# miscellaneous.net
KiCad netlist of a schematic drawn in Altium Designer
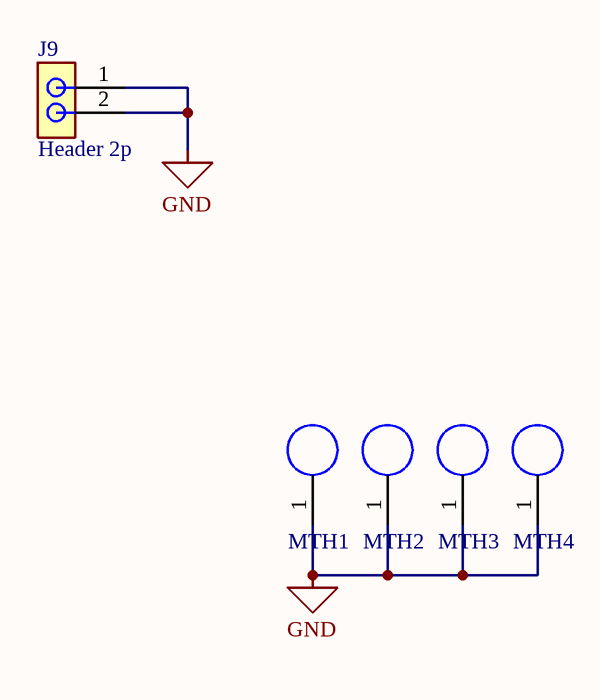
[diagram p0: miscellaneous.SchDoc]

(export (version "E")
  (design (tool "Eeschema 10.0.6"))
  (components
    (comp (ref "J9")
      (value "Header 2p")
      (footprint "Pin header 2p")
      (description "Connector")
      (fields
        (field (name "MANUFACTURER_PART_NUMBER") "DS1021-1*2SF11-B")
        (field (name "JLCPCB PART") "C492401")
      )
      (libsource (lib "Kubikova ultra knihovna") (part "Pin header 2p"))
    )
    (comp (ref "MTH1")
      (value "Hole")
      (footprint "3.2/6 MM")
      (description "Universal mounting hole plated")
      (libsource (lib "Kubikova ultra knihovna") (part "Hole"))
    )
    (comp (ref "MTH2")
      (value "Hole")
      (footprint "3.2/6 MM")
      (description "Universal mounting hole plated")
      (libsource (lib "Kubikova ultra knihovna") (part "Hole"))
    )
    (comp (ref "MTH3")
      (value "Hole")
      (footprint "3.2/6 MM")
      (description "Universal mounting hole plated")
      (libsource (lib "Kubikova ultra knihovna") (part "Hole"))
    )
    (comp (ref "MTH4")
      (value "Hole")
      (footprint "3.2/6 MM")
      (description "Universal mounting hole plated")
      (libsource (lib "Kubikova ultra knihovna") (part "Hole"))
    )
  )
  (nets
    (net (code "1") (name "GND") (class "Default")
      (node (ref "J9") (pin "1") (pinfunction "1_1") (pintype "passive"))
      (node (ref "J9") (pin "2") (pinfunction "2_2") (pintype "passive"))
      (node (ref "MTH1") (pin "1") (pintype "passive"))
      (node (ref "MTH2") (pin "1") (pintype "passive"))
      (node (ref "MTH3") (pin "1") (pintype "passive"))
      (node (ref "MTH4") (pin "1") (pintype "passive"))
    )
  )
)
